# M8-Relay-Dual-Latching.net
KiCad netlist of a schematic drawn in EAGLE
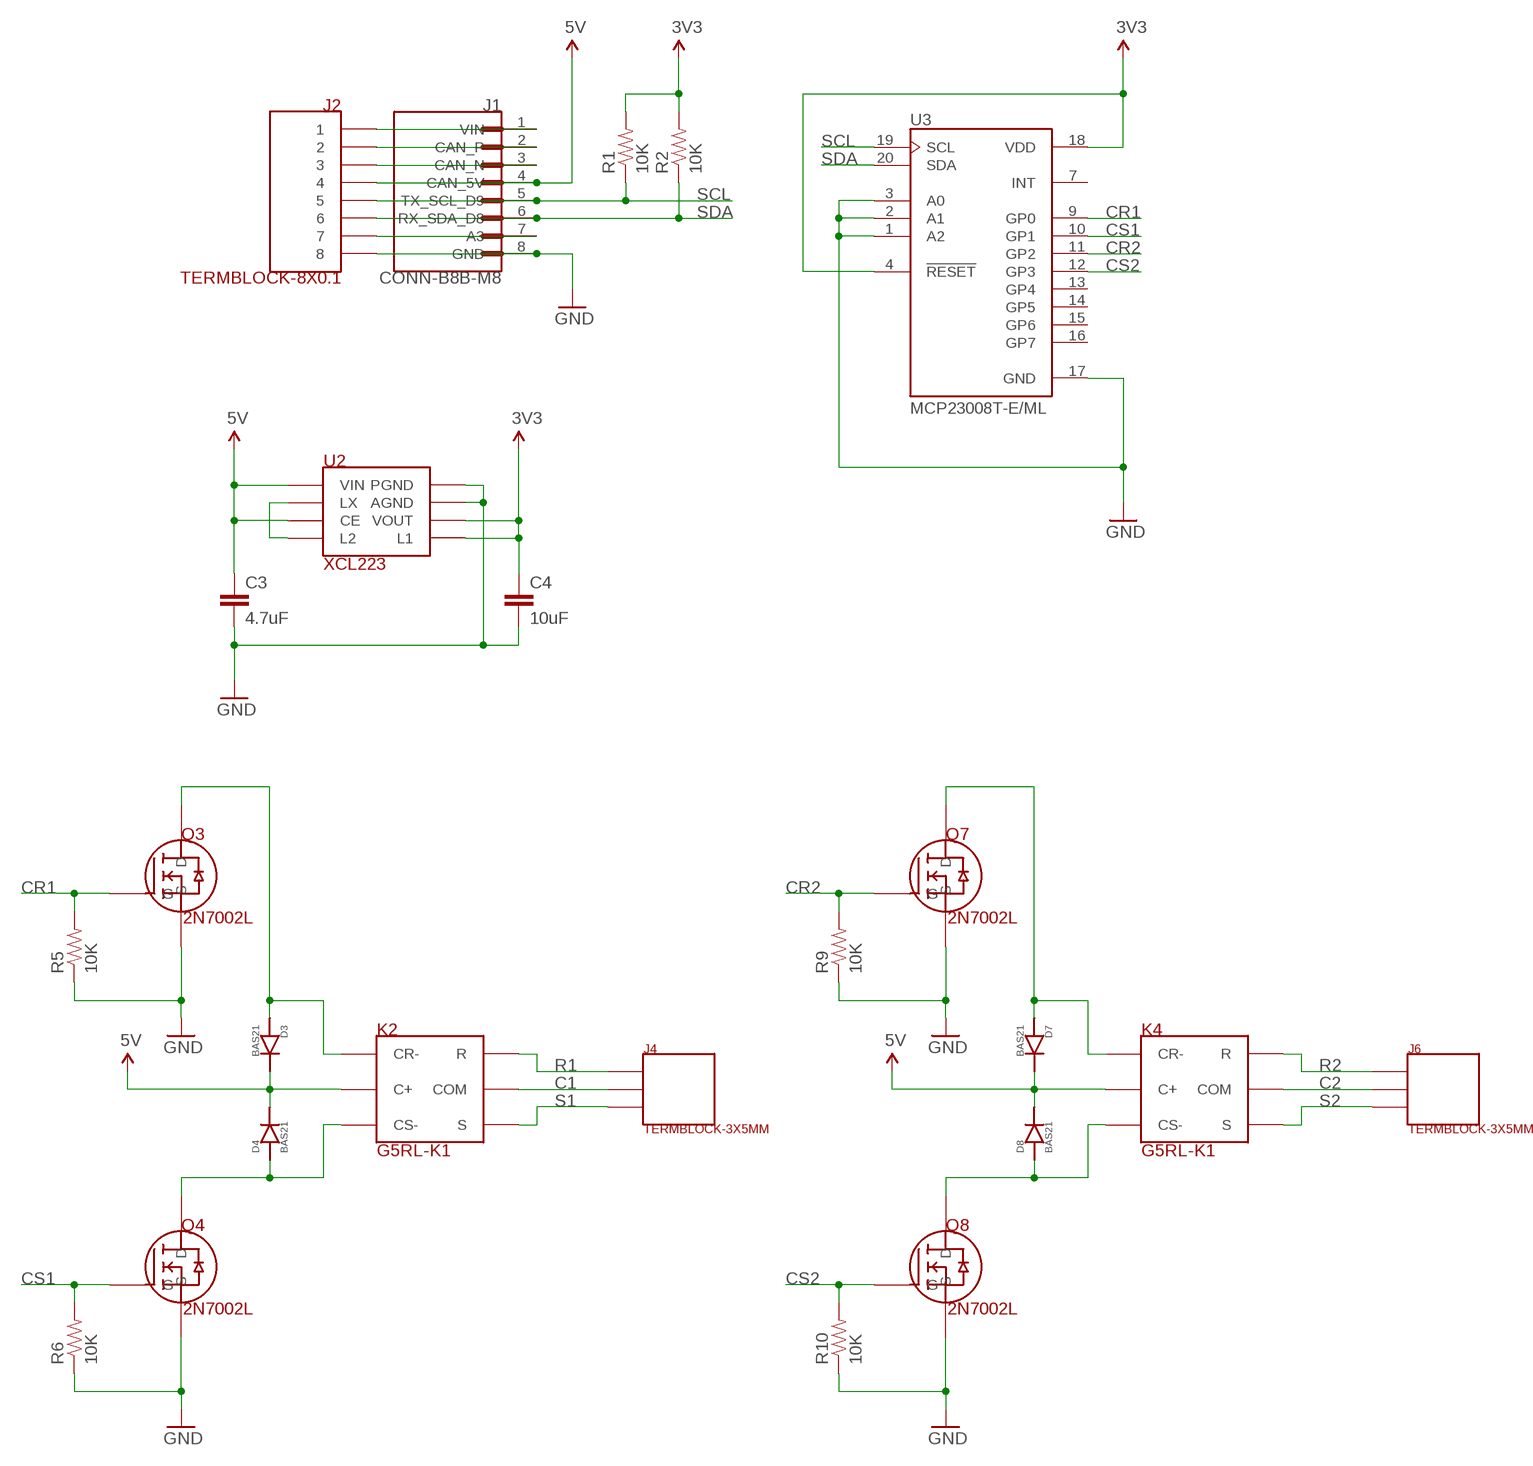
[diagram p0: schematic, sheet 1]

(export (version "E")
  (design (tool "Eeschema 10.0.6"))
  (components
    (comp (ref "C3")
      (value "4.7uF")
      (footprint "eagle-import:0603-CAP")
      (libsource (lib "eagle-import") (part "CAP-4.7UF-0603"))
    )
    (comp (ref "C4")
      (value "10uF")
      (footprint "eagle-import:0603-CAP")
      (libsource (lib "eagle-import") (part "CAP-10UF-0603"))
    )
    (comp (ref "D3")
      (value "BAS21")
      (footprint "eagle-import:DIODE-BAS21")
      (libsource (lib "eagle-import") (part "DIODE-BAS21"))
    )
    (comp (ref "D4")
      (value "BAS21")
      (footprint "eagle-import:DIODE-BAS21")
      (libsource (lib "eagle-import") (part "DIODE-BAS21"))
    )
    (comp (ref "D7")
      (value "BAS21")
      (footprint "eagle-import:DIODE-BAS21")
      (libsource (lib "eagle-import") (part "DIODE-BAS21"))
    )
    (comp (ref "D8")
      (value "BAS21")
      (footprint "eagle-import:DIODE-BAS21")
      (libsource (lib "eagle-import") (part "DIODE-BAS21"))
    )
    (comp (ref "J1")
      (value "CONN-B8B-M8")
      (footprint "eagle-import:JST_B8B-PH-SM4-TB(LF)(SN)")
      (libsource (lib "eagle-import") (part "CONN-B8B-M8"))
    )
    (comp (ref "J2")
      (value "TERMBLOCK-8X0.1")
      (footprint "eagle-import:TERMBLOCK-8X0.1")
      (libsource (lib "eagle-import") (part "TERMBLOCK-8X0.1"))
    )
    (comp (ref "J4")
      (value "TERMBLOCK-3X5MM")
      (footprint "eagle-import:TERMBLOCK-3X5MM")
      (libsource (lib "eagle-import") (part "TERMBLOCK-3X5MM"))
    )
    (comp (ref "J6")
      (value "TERMBLOCK-3X5MM")
      (footprint "eagle-import:TERMBLOCK-3X5MM")
      (libsource (lib "eagle-import") (part "TERMBLOCK-3X5MM"))
    )
    (comp (ref "K2")
      (value "G5RL-K1")
      (footprint "eagle-import:RELAY-G5RL-K1-E-LATCHING-SPDT")
      (libsource (lib "eagle-import") (part "RELAY-G5RL-K1-E-LATCHING-SPDT"))
    )
    (comp (ref "K4")
      (value "G5RL-K1")
      (footprint "eagle-import:RELAY-G5RL-K1-E-LATCHING-SPDT")
      (libsource (lib "eagle-import") (part "RELAY-G5RL-K1-E-LATCHING-SPDT"))
    )
    (comp (ref "Q3")
      (value "2N7002L")
      (footprint "eagle-import:2N7002L")
      (libsource (lib "eagle-import") (part "2N7002L"))
    )
    (comp (ref "Q4")
      (value "2N7002L")
      (footprint "eagle-import:2N7002L")
      (libsource (lib "eagle-import") (part "2N7002L"))
    )
    (comp (ref "Q7")
      (value "2N7002L")
      (footprint "eagle-import:2N7002L")
      (libsource (lib "eagle-import") (part "2N7002L"))
    )
    (comp (ref "Q8")
      (value "2N7002L")
      (footprint "eagle-import:2N7002L")
      (libsource (lib "eagle-import") (part "2N7002L"))
    )
    (comp (ref "R1")
      (value "10K")
      (footprint "eagle-import:0603-RES")
      (libsource (lib "eagle-import") (part "RES-10K-06030603"))
    )
    (comp (ref "R2")
      (value "10K")
      (footprint "eagle-import:0603-RES")
      (libsource (lib "eagle-import") (part "RES-10K-06030603"))
    )
    (comp (ref "R5")
      (value "10K")
      (footprint "eagle-import:0603-RES")
      (libsource (lib "eagle-import") (part "RES-10K-06030603"))
    )
    (comp (ref "R6")
      (value "10K")
      (footprint "eagle-import:0603-RES")
      (libsource (lib "eagle-import") (part "RES-10K-06030603"))
    )
    (comp (ref "R9")
      (value "10K")
      (footprint "eagle-import:0603-RES")
      (libsource (lib "eagle-import") (part "RES-10K-06030603"))
    )
    (comp (ref "R10")
      (value "10K")
      (footprint "eagle-import:0603-RES")
      (libsource (lib "eagle-import") (part "RES-10K-06030603"))
    )
    (comp (ref "U2")
      (value "XCL223")
      (footprint "eagle-import:REG-XCL223-LESS-CREAM")
      (libsource (lib "eagle-import") (part "REG-XCL223"))
    )
    (comp (ref "U3")
      (value "MCP23008T-E/ML")
      (footprint "eagle-import:QFN21P50_400X400X100L40X24T270N")
      (fields (field (name "MF") "Microchip Technology"))
      (libsource (lib "eagle-import") (part "MCP23008T-E/ML"))
    )
  )
  (nets
    (net (code "1") (name "/C1") (class "Default")
      (node (ref "J4") (pin "2") (pinfunction "2_2") (pintype "passive"))
      (node (ref "K2") (pin "3") (pinfunction "COM_3") (pintype "passive"))
      (node (ref "K2") (pin "6") (pinfunction "COM_6") (pintype "passive"))
    )
    (net (code "2") (name "/C2") (class "Default")
      (node (ref "J6") (pin "2") (pinfunction "2_2") (pintype "passive"))
      (node (ref "K4") (pin "3") (pinfunction "COM_3") (pintype "passive"))
      (node (ref "K4") (pin "6") (pinfunction "COM_6") (pintype "passive"))
    )
    (net (code "3") (name "/CR1") (class "Default")
      (node (ref "Q3") (pin "1") (pinfunction "G_1") (pintype "bidirectional"))
      (node (ref "R5") (pin "2") (pinfunction "2_2") (pintype "passive"))
      (node (ref "U3") (pin "9") (pinfunction "GP0_9") (pintype "bidirectional"))
    )
    (net (code "4") (name "/CR2") (class "Default")
      (node (ref "Q7") (pin "1") (pinfunction "G_1") (pintype "bidirectional"))
      (node (ref "R9") (pin "2") (pinfunction "2_2") (pintype "passive"))
      (node (ref "U3") (pin "11") (pinfunction "GP2_11") (pintype "bidirectional"))
    )
    (net (code "5") (name "/CS1") (class "Default")
      (node (ref "Q4") (pin "1") (pinfunction "G_1") (pintype "bidirectional"))
      (node (ref "R6") (pin "2") (pinfunction "2_2") (pintype "passive"))
      (node (ref "U3") (pin "10") (pinfunction "GP1_10") (pintype "bidirectional"))
    )
    (net (code "6") (name "/CS2") (class "Default")
      (node (ref "Q8") (pin "1") (pinfunction "G_1") (pintype "bidirectional"))
      (node (ref "R10") (pin "2") (pinfunction "2_2") (pintype "passive"))
      (node (ref "U3") (pin "12") (pinfunction "GP3_12") (pintype "bidirectional"))
    )
    (net (code "7") (name "/R1") (class "Default")
      (node (ref "J4") (pin "1") (pinfunction "1_1") (pintype "passive"))
      (node (ref "K2") (pin "2") (pinfunction "R_2") (pintype "passive"))
      (node (ref "K2") (pin "7") (pinfunction "R_7") (pintype "passive"))
    )
    (net (code "8") (name "/R2") (class "Default")
      (node (ref "J6") (pin "1") (pinfunction "1_1") (pintype "passive"))
      (node (ref "K4") (pin "2") (pinfunction "R_2") (pintype "passive"))
      (node (ref "K4") (pin "7") (pinfunction "R_7") (pintype "passive"))
    )
    (net (code "9") (name "/S1") (class "Default")
      (node (ref "J4") (pin "3") (pinfunction "3_3") (pintype "passive"))
      (node (ref "K2") (pin "4") (pinfunction "S_4") (pintype "passive"))
      (node (ref "K2") (pin "5") (pinfunction "S_5") (pintype "passive"))
    )
    (net (code "10") (name "/S2") (class "Default")
      (node (ref "J6") (pin "3") (pinfunction "3_3") (pintype "passive"))
      (node (ref "K4") (pin "4") (pinfunction "S_4") (pintype "passive"))
      (node (ref "K4") (pin "5") (pinfunction "S_5") (pintype "passive"))
    )
    (net (code "11") (name "/SCL") (class "Default")
      (node (ref "J1") (pin "5") (pinfunction "TX_SCL_D9_5") (pintype "passive"))
      (node (ref "J2") (pin "P$5") (pinfunction "5_P$5") (pintype "passive"))
      (node (ref "R1") (pin "1") (pinfunction "1_1") (pintype "passive"))
      (node (ref "U3") (pin "19") (pinfunction "SCL_19") (pintype "input"))
    )
    (net (code "12") (name "/SDA") (class "Default")
      (node (ref "J1") (pin "6") (pinfunction "RX_SDA_D8_6") (pintype "passive"))
      (node (ref "J2") (pin "P$6") (pinfunction "6_P$6") (pintype "passive"))
      (node (ref "R2") (pin "1") (pinfunction "1_1") (pintype "passive"))
      (node (ref "U3") (pin "20") (pinfunction "SDA_20") (pintype "bidirectional"))
    )
    (net (code "13") (name "3V3") (class "Default")
      (node (ref "C4") (pin "1") (pinfunction "1_1") (pintype "passive"))
      (node (ref "R1") (pin "2") (pinfunction "2_2") (pintype "passive"))
      (node (ref "R2") (pin "2") (pinfunction "2_2") (pintype "passive"))
      (node (ref "U2") (pin "3") (pinfunction "VOUT_3") (pintype "passive"))
      (node (ref "U2") (pin "7") (pinfunction "L1_7") (pintype "passive"))
      (node (ref "U3") (pin "18") (pinfunction "VDD_18") (pintype "power_in"))
      (node (ref "U3") (pin "4") (pinfunction "~{RESET}_4") (pintype "input"))
    )
    (net (code "14") (name "5V") (class "Default")
      (node (ref "C3") (pin "1") (pinfunction "1_1") (pintype "passive"))
      (node (ref "D3") (pin "3") (pinfunction "CATHODE_3") (pintype "bidirectional"))
      (node (ref "D4") (pin "3") (pinfunction "CATHODE_3") (pintype "bidirectional"))
      (node (ref "D7") (pin "3") (pinfunction "CATHODE_3") (pintype "bidirectional"))
      (node (ref "D8") (pin "3") (pinfunction "CATHODE_3") (pintype "bidirectional"))
      (node (ref "J1") (pin "4") (pinfunction "CAN_5V_4") (pintype "passive"))
      (node (ref "J2") (pin "P$4") (pinfunction "4_P$4") (pintype "passive"))
      (node (ref "K2") (pin "9") (pinfunction "C+_9") (pintype "input"))
      (node (ref "K4") (pin "9") (pinfunction "C+_9") (pintype "input"))
      (node (ref "U2") (pin "4") (pinfunction "CE_4") (pintype "input"))
      (node (ref "U2") (pin "6") (pinfunction "VIN_6") (pintype "power_in"))
    )
    (net (code "15") (name "GND") (class "Default")
      (node (ref "C3") (pin "2") (pinfunction "2_2") (pintype "passive"))
      (node (ref "C4") (pin "2") (pinfunction "2_2") (pintype "passive"))
      (node (ref "J1") (pin "8") (pinfunction "GND_8") (pintype "passive"))
      (node (ref "J2") (pin "P$8") (pinfunction "8_P$8") (pintype "passive"))
      (node (ref "Q3") (pin "2") (pinfunction "S_2") (pintype "bidirectional"))
      (node (ref "Q4") (pin "2") (pinfunction "S_2") (pintype "bidirectional"))
      (node (ref "Q7") (pin "2") (pinfunction "S_2") (pintype "bidirectional"))
      (node (ref "Q8") (pin "2") (pinfunction "S_2") (pintype "bidirectional"))
      (node (ref "R10") (pin "1") (pinfunction "1_1") (pintype "passive"))
      (node (ref "R5") (pin "1") (pinfunction "1_1") (pintype "passive"))
      (node (ref "R6") (pin "1") (pinfunction "1_1") (pintype "passive"))
      (node (ref "R9") (pin "1") (pinfunction "1_1") (pintype "passive"))
      (node (ref "U2") (pin "1") (pinfunction "PGND_1") (pintype "passive"))
      (node (ref "U2") (pin "2") (pinfunction "AGND_2") (pintype "passive"))
      (node (ref "U3") (pin "1") (pinfunction "A2_1") (pintype "bidirectional"))
      (node (ref "U3") (pin "17") (pinfunction "GND_17") (pintype "power_in"))
      (node (ref "U3") (pin "2") (pinfunction "A1_2") (pintype "input"))
      (node (ref "U3") (pin "3") (pinfunction "A0_3") (pintype "input"))
    )
    (net (code "16") (name "Net-(D3-ANODE)") (class "Default")
      (node (ref "D3") (pin "1") (pinfunction "ANODE_1") (pintype "bidirectional"))
      (node (ref "K2") (pin "1") (pinfunction "CR-_1") (pintype "input"))
      (node (ref "Q3") (pin "3") (pinfunction "D_3") (pintype "bidirectional"))
    )
    (net (code "17") (name "Net-(D4-ANODE)") (class "Default")
      (node (ref "D4") (pin "1") (pinfunction "ANODE_1") (pintype "bidirectional"))
      (node (ref "K2") (pin "8") (pinfunction "CS-_8") (pintype "input"))
      (node (ref "Q4") (pin "3") (pinfunction "D_3") (pintype "bidirectional"))
    )
    (net (code "18") (name "Net-(D7-ANODE)") (class "Default")
      (node (ref "D7") (pin "1") (pinfunction "ANODE_1") (pintype "bidirectional"))
      (node (ref "K4") (pin "1") (pinfunction "CR-_1") (pintype "input"))
      (node (ref "Q7") (pin "3") (pinfunction "D_3") (pintype "bidirectional"))
    )
    (net (code "19") (name "Net-(D8-ANODE)") (class "Default")
      (node (ref "D8") (pin "1") (pinfunction "ANODE_1") (pintype "bidirectional"))
      (node (ref "K4") (pin "8") (pinfunction "CS-_8") (pintype "input"))
      (node (ref "Q8") (pin "3") (pinfunction "D_3") (pintype "bidirectional"))
    )
    (net (code "20") (name "Net-(J1-A3)") (class "Default")
      (node (ref "J1") (pin "7") (pinfunction "A3_7") (pintype "passive"))
      (node (ref "J2") (pin "P$7") (pinfunction "7_P$7") (pintype "passive"))
    )
    (net (code "21") (name "Net-(J1-CAN_N)") (class "Default")
      (node (ref "J1") (pin "3") (pinfunction "CAN_N_3") (pintype "passive"))
      (node (ref "J2") (pin "P$3") (pinfunction "3_P$3") (pintype "passive"))
    )
    (net (code "22") (name "Net-(J1-CAN_P)") (class "Default")
      (node (ref "J1") (pin "2") (pinfunction "CAN_P_2") (pintype "passive"))
      (node (ref "J2") (pin "P$2") (pinfunction "2_P$2") (pintype "passive"))
    )
    (net (code "23") (name "Net-(J1-VIN)") (class "Default")
      (node (ref "J1") (pin "1") (pinfunction "VIN_1") (pintype "passive"))
      (node (ref "J2") (pin "P$1") (pinfunction "1_P$1") (pintype "passive"))
    )
    (net (code "24") (name "Net-(U2-L2)") (class "Default")
      (node (ref "U2") (pin "5") (pinfunction "LX_5") (pintype "passive"))
      (node (ref "U2") (pin "8") (pinfunction "L2_8") (pintype "passive"))
    )
    (net (code "25") (name "unconnected-(U3-GP4-Pad13)") (class "Default")
      (node (ref "U3") (pin "13") (pinfunction "GP4_13") (pintype "bidirectional"))
    )
    (net (code "26") (name "unconnected-(U3-GP5-Pad14)") (class "Default")
      (node (ref "U3") (pin "14") (pinfunction "GP5_14") (pintype "bidirectional"))
    )
    (net (code "27") (name "unconnected-(U3-GP6-Pad15)") (class "Default")
      (node (ref "U3") (pin "15") (pinfunction "GP6_15") (pintype "bidirectional"))
    )
    (net (code "28") (name "unconnected-(U3-GP7-Pad16)") (class "Default")
      (node (ref "U3") (pin "16") (pinfunction "GP7_16") (pintype "bidirectional"))
    )
    (net (code "29") (name "unconnected-(U3-INT-Pad7)") (class "Default")
      (node (ref "U3") (pin "7") (pinfunction "INT_7") (pintype "output"))
    )
  )
)
